# dlr.net
KiCad netlist of a schematic drawn in EAGLE
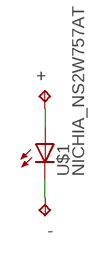
[diagram p0: schematic, sheet 1]

(export (version "E")
  (design (tool "Eeschema 10.0.6"))
  (components
    (comp (ref "+")
      (value "TPTP20SQ")
      (footprint "eagle-import:TP20SQ")
      (libsource (lib "eagle-import") (part "TPTP20SQ"))
    )
    (comp (ref "-")
      (value "TPTP20SQ")
      (footprint "eagle-import:TP20SQ")
      (libsource (lib "eagle-import") (part "TPTP20SQ"))
    )
    (comp (ref "U$1")
      (value "NICHIA_NS2W757AT")
      (footprint "eagle-import:NICHIA_NS2W757AT")
      (libsource (lib "eagle-import") (part "NICHIA_NS2W757AT"))
    )
  )
  (nets
    (net (code "1") (name "Net-(U$1-A)") (class "Default")
      (node (ref "+") (pin "TP") (pinfunction "TP_TP") (pintype "input"))
      (node (ref "U$1") (pin "ANODE") (pinfunction "A_ANODE") (pintype "passive"))
    )
    (net (code "2") (name "Net-(U$1-C)") (class "Default")
      (node (ref "-") (pin "TP") (pinfunction "TP_TP") (pintype "input"))
      (node (ref "U$1") (pin "CATHODE") (pinfunction "C_CATHODE") (pintype "passive"))
    )
  )
)
